# X_Axis_Stepper_Motor_Driver.net
KiCad netlist of a schematic drawn in Altium Designer
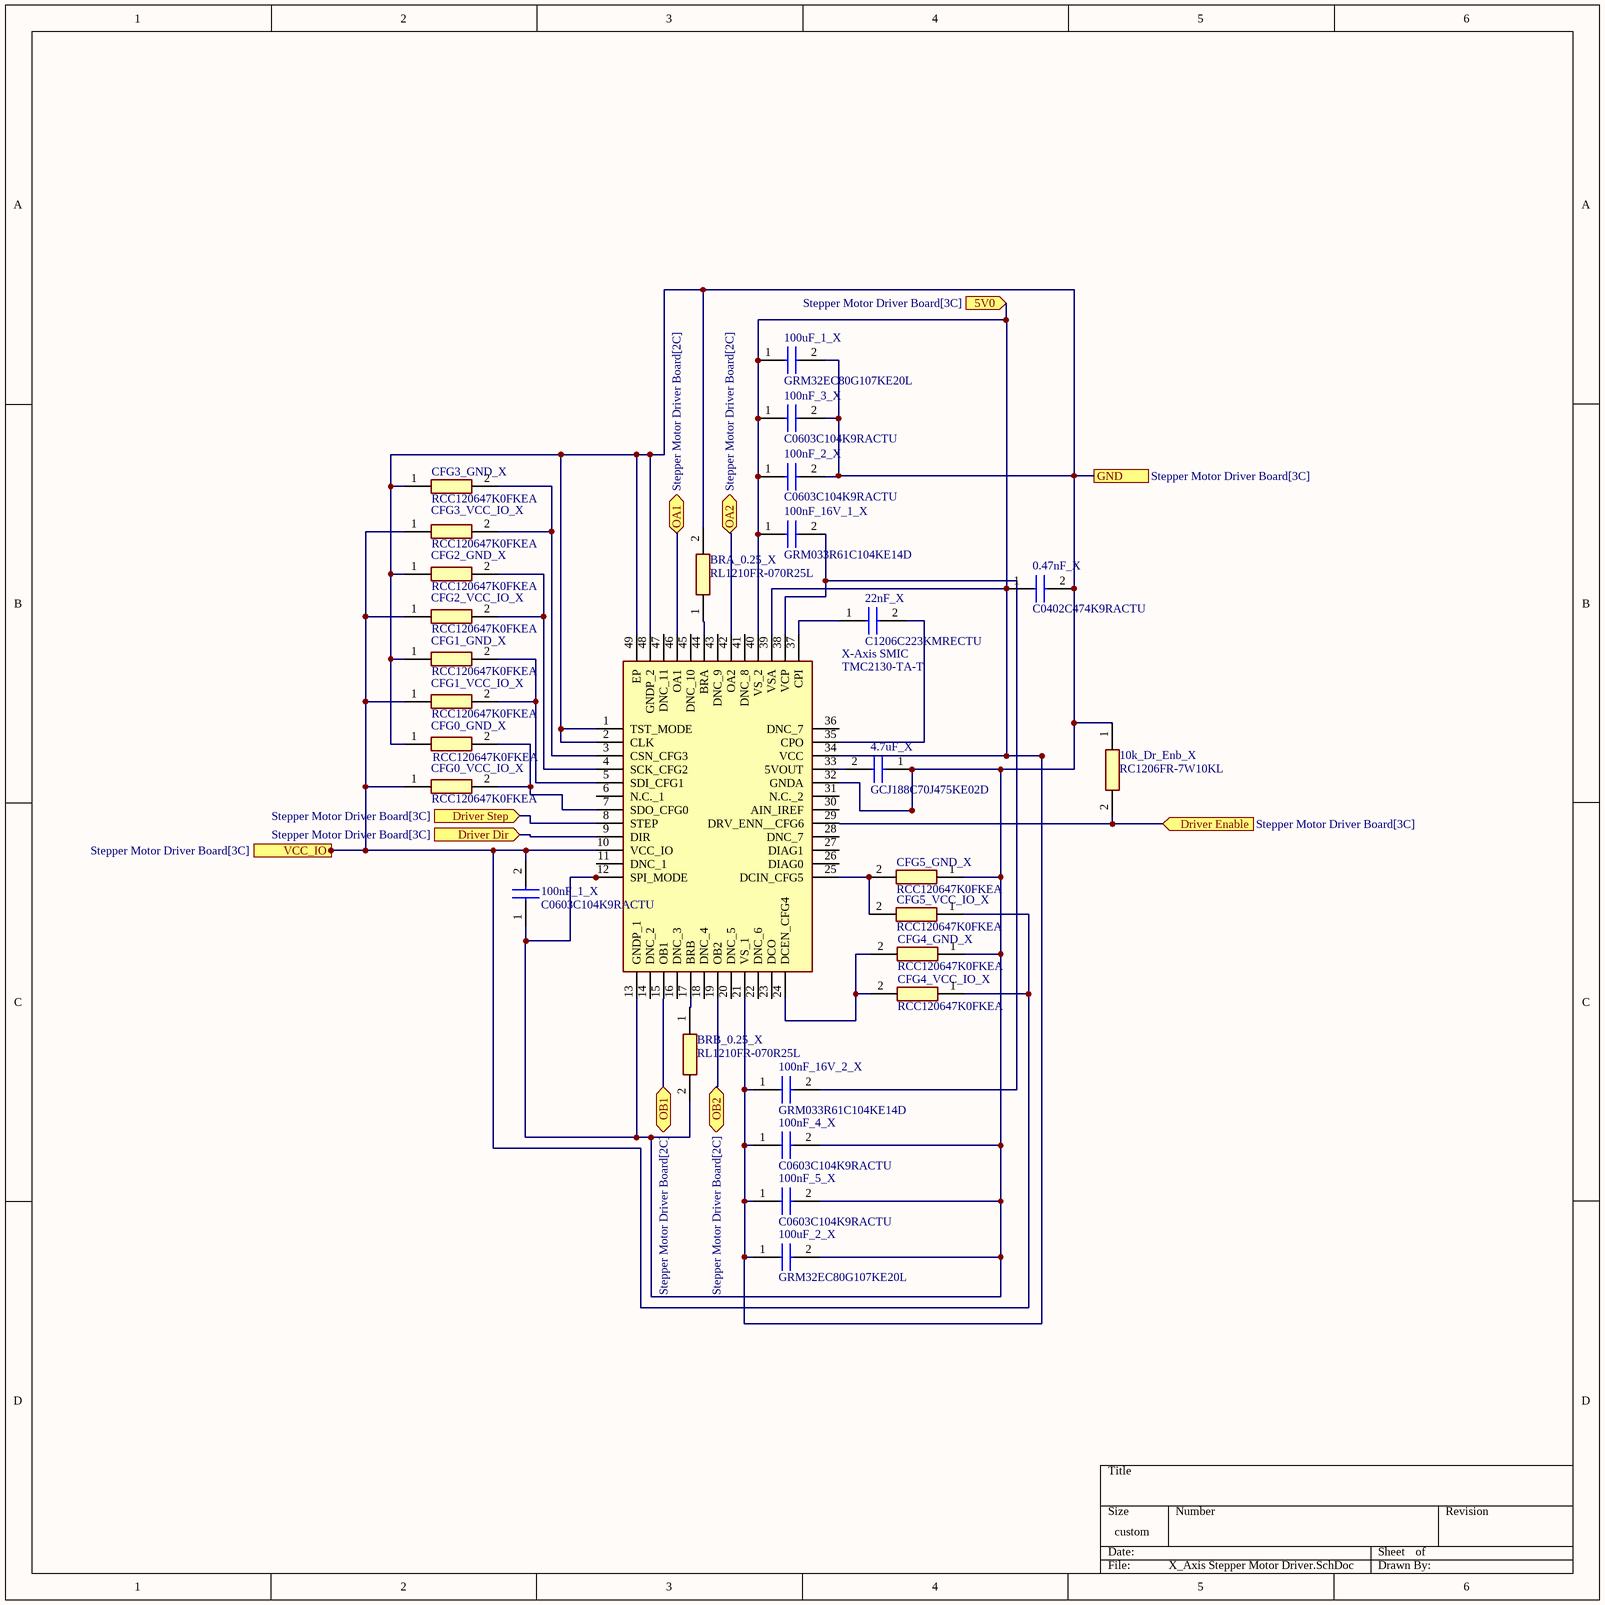
[diagram p0: X_Axis Stepper Motor Driver.SchDoc]

(export (version "E")
  (design (tool "Eeschema 10.0.6"))
  (components
    (comp (ref "0.47nF_X")
      (value "C0402C474K9RACTU")
      (footprint "SamacSys:CAPC1005X55N")
      (description "Capacitor")
      (fields (field (name "MOUSER PART NUMBER") "80-C0402C474K9RACTU"))
      (libsource (lib "*") (part "C0402C474K9RACTU"))
    )
    (comp (ref "4.7uF_X")
      (value "GCJ188C70J475KE02D")
      (footprint "SamacSys:CAPC1608X100N")
      (description "Capacitor")
      (fields (field (name "MOUSER PART NUMBER") "81-GCJ188C70J475KE2D"))
      (libsource (lib "*") (part "GCJ188C70J475KE02D"))
    )
    (comp (ref "10k_Dr_Enb_X")
      (value "RC1206FR-7W10KL")
      (footprint "SamacSys:RESC3116X65N")
      (description "Resistor")
      (libsource (lib "*") (part "RC1206FR-7W10KL"))
    )
    (comp (ref "22nF_X")
      (value "C1206C223KMRECTU")
      (footprint "SamacSys:C1206")
      (description "Capacitor")
      (fields (field (name "MOUSER PART NUMBER") "80-C1206C223KMRECTU"))
      (libsource (lib "*") (part "C1206C223KMRECTU"))
    )
    (comp (ref "100nF_1_X")
      (value "C0603C104K9RACTU")
      (footprint "SamacSys:C0603")
      (description "Capacitor")
      (fields (field (name "MOUSER PART NUMBER") "80-C0603C104K9R"))
      (libsource (lib "*") (part "C0603C104K9RACTU"))
    )
    (comp (ref "100nF_2_X")
      (value "C0603C104K9RACTU")
      (footprint "SamacSys:C0603")
      (description "Capacitor")
      (fields (field (name "MOUSER PART NUMBER") "80-C0603C104K9R"))
      (libsource (lib "*") (part "C0603C104K9RACTU"))
    )
    (comp (ref "100nF_3_X")
      (value "C0603C104K9RACTU")
      (footprint "SamacSys:C0603")
      (description "Capacitor")
      (fields (field (name "MOUSER PART NUMBER") "80-C0603C104K9R"))
      (libsource (lib "*") (part "C0603C104K9RACTU"))
    )
    (comp (ref "100nF_4_X")
      (value "C0603C104K9RACTU")
      (footprint "SamacSys:C0603")
      (description "Capacitor")
      (fields (field (name "MOUSER PART NUMBER") "80-C0603C104K9R"))
      (libsource (lib "*") (part "C0603C104K9RACTU"))
    )
    (comp (ref "100nF_5_X")
      (value "C0603C104K9RACTU")
      (footprint "SamacSys:C0603")
      (description "Capacitor")
      (fields (field (name "MOUSER PART NUMBER") "80-C0603C104K9R"))
      (libsource (lib "*") (part "C0603C104K9RACTU"))
    )
    (comp (ref "100nF_16V_1_X")
      (value "GRM033R61C104KE14D")
      (footprint "SamacSys:CAPC0603X33N")
      (description "Capacitor")
      (fields (field (name "MOUSER PART NUMBER") "81-GRM033R61C104KE4D"))
      (libsource (lib "*") (part "GRM033R61C104KE14D"))
    )
    (comp (ref "100nF_16V_2_X")
      (value "GRM033R61C104KE14D")
      (footprint "SamacSys:CAPC0603X33N")
      (description "Capacitor")
      (fields (field (name "MOUSER PART NUMBER") "81-GRM033R61C104KE4D"))
      (libsource (lib "*") (part "GRM033R61C104KE14D"))
    )
    (comp (ref "100uF_1_X")
      (value "GRM32EC80G107KE20L")
      (footprint "SamacSys:CAPC3225X270N")
      (description "Capacitor")
      (fields (field (name "MOUSER PART NUMBER") "81-GRM32EC80G107KE0L"))
      (libsource (lib "*") (part "GRM32EC80G107KE20L"))
    )
    (comp (ref "100uF_2_X")
      (value "GRM32EC80G107KE20L")
      (footprint "SamacSys:CAPC3225X270N")
      (description "Capacitor")
      (fields (field (name "MOUSER PART NUMBER") "81-GRM32EC80G107KE0L"))
      (libsource (lib "*") (part "GRM32EC80G107KE20L"))
    )
    (comp (ref "BRA_0.25_X")
      (value "RL1210FR-070R25L")
      (footprint "SamacSys:RESC3126X65N")
      (description "Resistor")
      (fields (field (name "MOUSER PART NUMBER") "603-RL1210FR-070R25L"))
      (libsource (lib "") (part "RL1210FR-070R25L_1"))
    )
    (comp (ref "BRB_0.25_X")
      (value "RL1210FR-070R25L")
      (footprint "SamacSys:RESC3126X65N")
      (description "Resistor")
      (fields (field (name "MOUSER PART NUMBER") "603-RL1210FR-070R25L"))
      (libsource (lib "*") (part "RL1210FR-070R25L"))
    )
    (comp (ref "CFG0_GND_X")
      (value "RCC120647K0FKEA")
      (footprint "SamacSys:RCC1206_e3")
      (description "Resistor")
      (fields (field (name "MOUSER PART NUMBER") "71-RCC120647K0FKEA"))
      (libsource (lib "") (part "RCC120647K0FKEA_1"))
    )
    (comp (ref "CFG0_VCC_IO_X")
      (value "RCC120647K0FKEA")
      (footprint "SamacSys:RCC1206_e3")
      (description "Resistor")
      (fields (field (name "MOUSER PART NUMBER") "71-RCC120647K0FKEA"))
      (libsource (lib "") (part "RCC120647K0FKEA_1"))
    )
    (comp (ref "CFG1_GND_X")
      (value "RCC120647K0FKEA")
      (footprint "SamacSys:RCC1206_e3")
      (description "Resistor")
      (fields (field (name "MOUSER PART NUMBER") "71-RCC120647K0FKEA"))
      (libsource (lib "") (part "RCC120647K0FKEA_1"))
    )
    (comp (ref "CFG1_VCC_IO_X")
      (value "RCC120647K0FKEA")
      (footprint "SamacSys:RCC1206_e3")
      (description "Resistor")
      (fields (field (name "MOUSER PART NUMBER") "71-RCC120647K0FKEA"))
      (libsource (lib "") (part "RCC120647K0FKEA_1"))
    )
    (comp (ref "CFG2_GND_X")
      (value "RCC120647K0FKEA")
      (footprint "SamacSys:RCC1206_e3")
      (description "Resistor")
      (fields (field (name "MOUSER PART NUMBER") "71-RCC120647K0FKEA"))
      (libsource (lib "") (part "RCC120647K0FKEA_1"))
    )
    (comp (ref "CFG2_VCC_IO_X")
      (value "RCC120647K0FKEA")
      (footprint "SamacSys:RCC1206_e3")
      (description "Resistor")
      (fields (field (name "MOUSER PART NUMBER") "71-RCC120647K0FKEA"))
      (libsource (lib "") (part "RCC120647K0FKEA_1"))
    )
    (comp (ref "CFG3_GND_X")
      (value "RCC120647K0FKEA")
      (footprint "SamacSys:RCC1206_e3")
      (description "Resistor")
      (fields (field (name "MOUSER PART NUMBER") "71-RCC120647K0FKEA"))
      (libsource (lib "") (part "RCC120647K0FKEA_1"))
    )
    (comp (ref "CFG3_VCC_IO_X")
      (value "RCC120647K0FKEA")
      (footprint "SamacSys:RCC1206_e3")
      (description "Resistor")
      (fields (field (name "MOUSER PART NUMBER") "71-RCC120647K0FKEA"))
      (libsource (lib "") (part "RCC120647K0FKEA_1"))
    )
    (comp (ref "CFG4_GND_X")
      (value "RCC120647K0FKEA")
      (footprint "SamacSys:RCC1206_e3")
      (description "Resistor")
      (fields (field (name "MOUSER PART NUMBER") "71-RCC120647K0FKEA"))
      (libsource (lib "*") (part "RCC120647K0FKEA"))
    )
    (comp (ref "CFG4_VCC_IO_X")
      (value "RCC120647K0FKEA")
      (footprint "SamacSys:RCC1206_e3")
      (description "Resistor")
      (fields (field (name "MOUSER PART NUMBER") "71-RCC120647K0FKEA"))
      (libsource (lib "*") (part "RCC120647K0FKEA"))
    )
    (comp (ref "CFG5_GND_X")
      (value "RCC120647K0FKEA")
      (footprint "SamacSys:RCC1206_e3")
      (description "Resistor")
      (fields (field (name "MOUSER PART NUMBER") "71-RCC120647K0FKEA"))
      (libsource (lib "") (part "RCC120647K0FKEA_2"))
    )
    (comp (ref "CFG5_VCC_IO_X")
      (value "RCC120647K0FKEA")
      (footprint "SamacSys:RCC1206_e3")
      (description "Resistor")
      (fields (field (name "MOUSER PART NUMBER") "71-RCC120647K0FKEA"))
      (libsource (lib "*") (part "RCC120647K0FKEA"))
    )
    (comp (ref "X-Axis SMIC")
      (value "TMC2130-TA-T")
      (footprint "SamacSys:QFP50P900X900X120-49N")
      (description "Integrated Circuit")
      (fields (field (name "MOUSER PART NUMBER") "700-TMC2130-TA-T"))
      (libsource (lib "*") (part "TMC2130-TA-T"))
    )
  )
  (nets
    (net (code "1") (name "/5V0") (class "Default")
      (node (ref "0.47nF_X") (pin "1") (pinfunction "1_1") (pintype "passive"))
      (node (ref "100nF_16V_1_X") (pin "1") (pinfunction "1_1") (pintype "passive"))
      (node (ref "100nF_16V_2_X") (pin "1") (pinfunction "1_1") (pintype "passive"))
      (node (ref "100nF_2_X") (pin "1") (pinfunction "1_1") (pintype "passive"))
      (node (ref "100nF_3_X") (pin "1") (pinfunction "1_1") (pintype "passive"))
      (node (ref "100nF_4_X") (pin "1") (pinfunction "1_1") (pintype "passive"))
      (node (ref "100nF_5_X") (pin "1") (pinfunction "1_1") (pintype "passive"))
      (node (ref "100uF_1_X") (pin "1") (pinfunction "1_1") (pintype "passive"))
      (node (ref "100uF_2_X") (pin "1") (pinfunction "1_1") (pintype "passive"))
      (node (ref "X-Axis SMIC") (pin "21") (pinfunction "VS_1_21") (pintype "passive"))
      (node (ref "X-Axis SMIC") (pin "34") (pinfunction "VCC_34") (pintype "passive"))
      (node (ref "X-Axis SMIC") (pin "39") (pinfunction "VSA_39") (pintype "passive"))
      (node (ref "X-Axis SMIC") (pin "40") (pinfunction "VS_2_40") (pintype "passive"))
    )
    (net (code "2") (name "/Driver Dir") (class "Default")
      (node (ref "X-Axis SMIC") (pin "9") (pinfunction "DIR_9") (pintype "passive"))
    )
    (net (code "3") (name "/Driver Enable") (class "Default")
      (node (ref "10k_Dr_Enb_X") (pin "2") (pinfunction "2_2") (pintype "passive"))
      (node (ref "X-Axis SMIC") (pin "29") (pinfunction "DRV_ENN__CFG6_29") (pintype "passive"))
    )
    (net (code "4") (name "/Driver Step") (class "Default")
      (node (ref "X-Axis SMIC") (pin "8") (pinfunction "STEP_8") (pintype "passive"))
    )
    (net (code "5") (name "/GND") (class "Default")
      (node (ref "0.47nF_X") (pin "2") (pinfunction "2_2") (pintype "passive"))
      (node (ref "100nF_1_X") (pin "1") (pinfunction "1_1") (pintype "passive"))
      (node (ref "100nF_2_X") (pin "2") (pinfunction "2_2") (pintype "passive"))
      (node (ref "100nF_3_X") (pin "2") (pinfunction "2_2") (pintype "passive"))
      (node (ref "100nF_4_X") (pin "2") (pinfunction "2_2") (pintype "passive"))
      (node (ref "100nF_5_X") (pin "2") (pinfunction "2_2") (pintype "passive"))
      (node (ref "100uF_1_X") (pin "2") (pinfunction "2_2") (pintype "passive"))
      (node (ref "100uF_2_X") (pin "2") (pinfunction "2_2") (pintype "passive"))
      (node (ref "10k_Dr_Enb_X") (pin "1") (pinfunction "1_1") (pintype "passive"))
      (node (ref "4.7uF_X") (pin "1") (pinfunction "1_1") (pintype "passive"))
      (node (ref "BRA_0.25_X") (pin "2") (pinfunction "2_2") (pintype "passive"))
      (node (ref "BRB_0.25_X") (pin "2") (pinfunction "2_2") (pintype "passive"))
      (node (ref "CFG0_GND_X") (pin "1") (pinfunction "1_1") (pintype "passive"))
      (node (ref "CFG1_GND_X") (pin "1") (pinfunction "1_1") (pintype "passive"))
      (node (ref "CFG2_GND_X") (pin "1") (pinfunction "1_1") (pintype "passive"))
      (node (ref "CFG3_GND_X") (pin "1") (pinfunction "1_1") (pintype "passive"))
      (node (ref "CFG4_GND_X") (pin "1") (pinfunction "1_1") (pintype "passive"))
      (node (ref "CFG5_GND_X") (pin "1") (pinfunction "1_1") (pintype "passive"))
      (node (ref "X-Axis SMIC") (pin "1") (pinfunction "TST_MODE_1") (pintype "passive"))
      (node (ref "X-Axis SMIC") (pin "12") (pinfunction "SPI_MODE_12") (pintype "passive"))
      (node (ref "X-Axis SMIC") (pin "13") (pinfunction "GNDP_1_13") (pintype "passive"))
      (node (ref "X-Axis SMIC") (pin "2") (pinfunction "CLK_2") (pintype "passive"))
      (node (ref "X-Axis SMIC") (pin "32") (pinfunction "GNDA_32") (pintype "passive"))
      (node (ref "X-Axis SMIC") (pin "48") (pinfunction "GNDP_2_48") (pintype "passive"))
      (node (ref "X-Axis SMIC") (pin "49") (pinfunction "EP_49") (pintype "passive"))
    )
    (net (code "6") (name "/OA1") (class "Default")
      (node (ref "X-Axis SMIC") (pin "46") (pinfunction "OA1_46") (pintype "passive"))
    )
    (net (code "7") (name "/OA2") (class "Default")
      (node (ref "X-Axis SMIC") (pin "42") (pinfunction "OA2_42") (pintype "passive"))
    )
    (net (code "8") (name "/OB1") (class "Default")
      (node (ref "X-Axis SMIC") (pin "15") (pinfunction "OB1_15") (pintype "passive"))
    )
    (net (code "9") (name "/OB2") (class "Default")
      (node (ref "X-Axis SMIC") (pin "19") (pinfunction "OB2_19") (pintype "passive"))
    )
    (net (code "10") (name "/VCC_IO") (class "Default")
      (node (ref "100nF_1_X") (pin "2") (pinfunction "2_2") (pintype "passive"))
      (node (ref "CFG0_VCC_IO_X") (pin "1") (pinfunction "1_1") (pintype "passive"))
      (node (ref "CFG1_VCC_IO_X") (pin "1") (pinfunction "1_1") (pintype "passive"))
      (node (ref "CFG2_VCC_IO_X") (pin "1") (pinfunction "1_1") (pintype "passive"))
      (node (ref "CFG3_VCC_IO_X") (pin "1") (pinfunction "1_1") (pintype "passive"))
      (node (ref "CFG4_VCC_IO_X") (pin "1") (pinfunction "1_1") (pintype "passive"))
      (node (ref "CFG5_VCC_IO_X") (pin "1") (pinfunction "1_1") (pintype "passive"))
      (node (ref "X-Axis SMIC") (pin "10") (pinfunction "VCC_IO_10") (pintype "passive"))
    )
    (net (code "11") (name "Net-(X-Axis SMIC-5VOUT)") (class "Default")
      (node (ref "4.7uF_X") (pin "2") (pinfunction "2_2") (pintype "passive"))
      (node (ref "X-Axis SMIC") (pin "33") (pinfunction "5VOUT_33") (pintype "passive"))
    )
    (net (code "12") (name "Net-(X-Axis SMIC-BRA)") (class "Default")
      (node (ref "BRA_0.25_X") (pin "1") (pinfunction "1_1") (pintype "passive"))
      (node (ref "X-Axis SMIC") (pin "44") (pinfunction "BRA_44") (pintype "passive"))
    )
    (net (code "13") (name "Net-(X-Axis SMIC-BRB)") (class "Default")
      (node (ref "BRB_0.25_X") (pin "1") (pinfunction "1_1") (pintype "passive"))
      (node (ref "X-Axis SMIC") (pin "17") (pinfunction "BRB_17") (pintype "passive"))
    )
    (net (code "14") (name "Net-(X-Axis SMIC-CPI)") (class "Default")
      (node (ref "22nF_X") (pin "1") (pinfunction "1_1") (pintype "passive"))
      (node (ref "X-Axis SMIC") (pin "37") (pinfunction "CPI_37") (pintype "passive"))
    )
    (net (code "15") (name "Net-(X-Axis SMIC-CPO)") (class "Default")
      (node (ref "22nF_X") (pin "2") (pinfunction "2_2") (pintype "passive"))
      (node (ref "X-Axis SMIC") (pin "35") (pinfunction "CPO_35") (pintype "passive"))
    )
    (net (code "16") (name "Net-(X-Axis SMIC-CSN_CFG3)") (class "Default")
      (node (ref "CFG3_GND_X") (pin "2") (pinfunction "2_2") (pintype "passive"))
      (node (ref "CFG3_VCC_IO_X") (pin "2") (pinfunction "2_2") (pintype "passive"))
      (node (ref "X-Axis SMIC") (pin "3") (pinfunction "CSN_CFG3_3") (pintype "passive"))
    )
    (net (code "17") (name "Net-(X-Axis SMIC-DCEN_CFG4)") (class "Default")
      (node (ref "CFG4_GND_X") (pin "2") (pinfunction "2_2") (pintype "passive"))
      (node (ref "CFG4_VCC_IO_X") (pin "2") (pinfunction "2_2") (pintype "passive"))
      (node (ref "X-Axis SMIC") (pin "24") (pinfunction "DCEN_CFG4_24") (pintype "passive"))
    )
    (net (code "18") (name "Net-(X-Axis SMIC-DCIN_CFG5)") (class "Default")
      (node (ref "CFG5_GND_X") (pin "2") (pinfunction "2_2") (pintype "passive"))
      (node (ref "CFG5_VCC_IO_X") (pin "2") (pinfunction "2_2") (pintype "passive"))
      (node (ref "X-Axis SMIC") (pin "25") (pinfunction "DCIN_CFG5_25") (pintype "passive"))
    )
    (net (code "19") (name "Net-(X-Axis SMIC-SCK_CFG2)") (class "Default")
      (node (ref "CFG2_GND_X") (pin "2") (pinfunction "2_2") (pintype "passive"))
      (node (ref "CFG2_VCC_IO_X") (pin "2") (pinfunction "2_2") (pintype "passive"))
      (node (ref "X-Axis SMIC") (pin "4") (pinfunction "SCK_CFG2_4") (pintype "passive"))
    )
    (net (code "20") (name "Net-(X-Axis SMIC-SDI_CFG1)") (class "Default")
      (node (ref "CFG1_GND_X") (pin "2") (pinfunction "2_2") (pintype "passive"))
      (node (ref "CFG1_VCC_IO_X") (pin "2") (pinfunction "2_2") (pintype "passive"))
      (node (ref "X-Axis SMIC") (pin "5") (pinfunction "SDI_CFG1_5") (pintype "passive"))
    )
    (net (code "21") (name "Net-(X-Axis SMIC-SDO_CFG0)") (class "Default")
      (node (ref "CFG0_GND_X") (pin "2") (pinfunction "2_2") (pintype "passive"))
      (node (ref "CFG0_VCC_IO_X") (pin "2") (pinfunction "2_2") (pintype "passive"))
      (node (ref "X-Axis SMIC") (pin "7") (pinfunction "SDO_CFG0_7") (pintype "passive"))
    )
    (net (code "22") (name "Net-(X-Axis SMIC-VCP)") (class "Default")
      (node (ref "100nF_16V_1_X") (pin "2") (pinfunction "2_2") (pintype "passive"))
      (node (ref "100nF_16V_2_X") (pin "2") (pinfunction "2_2") (pintype "passive"))
      (node (ref "X-Axis SMIC") (pin "38") (pinfunction "VCP_38") (pintype "passive"))
    )
    (net (code "23") (name "unconnected-(X-Axis SMIC-AIN_IREF-Pad30)") (class "Default")
      (node (ref "X-Axis SMIC") (pin "30") (pinfunction "AIN_IREF_30") (pintype "passive"))
    )
    (net (code "24") (name "unconnected-(X-Axis SMIC-DCO-Pad23)") (class "Default")
      (node (ref "X-Axis SMIC") (pin "23") (pinfunction "DCO_23") (pintype "passive"))
    )
    (net (code "25") (name "unconnected-(X-Axis SMIC-DIAG0-Pad26)") (class "Default")
      (node (ref "X-Axis SMIC") (pin "26") (pinfunction "DIAG0_26") (pintype "passive"))
    )
    (net (code "26") (name "unconnected-(X-Axis SMIC-DIAG1-Pad27)") (class "Default")
      (node (ref "X-Axis SMIC") (pin "27") (pinfunction "DIAG1_27") (pintype "passive"))
    )
    (net (code "27") (name "unconnected-(X-Axis SMIC-DNC_1-Pad11)") (class "Default")
      (node (ref "X-Axis SMIC") (pin "11") (pinfunction "DNC_1_11") (pintype "passive"))
    )
    (net (code "28") (name "unconnected-(X-Axis SMIC-DNC_2-Pad14)") (class "Default")
      (node (ref "X-Axis SMIC") (pin "14") (pinfunction "DNC_2_14") (pintype "passive"))
    )
    (net (code "29") (name "unconnected-(X-Axis SMIC-DNC_3-Pad16)") (class "Default")
      (node (ref "X-Axis SMIC") (pin "16") (pinfunction "DNC_3_16") (pintype "passive"))
    )
    (net (code "30") (name "unconnected-(X-Axis SMIC-DNC_4-Pad18)") (class "Default")
      (node (ref "X-Axis SMIC") (pin "18") (pinfunction "DNC_4_18") (pintype "passive"))
    )
    (net (code "31") (name "unconnected-(X-Axis SMIC-DNC_5-Pad20)") (class "Default")
      (node (ref "X-Axis SMIC") (pin "20") (pinfunction "DNC_5_20") (pintype "passive"))
    )
    (net (code "32") (name "unconnected-(X-Axis SMIC-DNC_6-Pad22)") (class "Default")
      (node (ref "X-Axis SMIC") (pin "22") (pinfunction "DNC_6_22") (pintype "passive"))
    )
    (net (code "33") (name "unconnected-(X-Axis SMIC-DNC_7-Pad28)") (class "Default")
      (node (ref "X-Axis SMIC") (pin "28") (pinfunction "DNC_7_28") (pintype "passive"))
    )
    (net (code "34") (name "unconnected-(X-Axis SMIC-DNC_7-Pad36)") (class "Default")
      (node (ref "X-Axis SMIC") (pin "36") (pinfunction "DNC_7_36") (pintype "passive"))
    )
    (net (code "35") (name "unconnected-(X-Axis SMIC-DNC_8-Pad41)") (class "Default")
      (node (ref "X-Axis SMIC") (pin "41") (pinfunction "DNC_8_41") (pintype "passive"))
    )
    (net (code "36") (name "unconnected-(X-Axis SMIC-DNC_9-Pad43)") (class "Default")
      (node (ref "X-Axis SMIC") (pin "43") (pinfunction "DNC_9_43") (pintype "passive"))
    )
    (net (code "37") (name "unconnected-(X-Axis SMIC-DNC_10-Pad45)") (class "Default")
      (node (ref "X-Axis SMIC") (pin "45") (pinfunction "DNC_10_45") (pintype "passive"))
    )
    (net (code "38") (name "unconnected-(X-Axis SMIC-DNC_11-Pad47)") (class "Default")
      (node (ref "X-Axis SMIC") (pin "47") (pinfunction "DNC_11_47") (pintype "passive"))
    )
    (net (code "39") (name "unconnected-(X-Axis SMIC-N.C._1-Pad6)") (class "Default")
      (node (ref "X-Axis SMIC") (pin "6") (pinfunction "N.C._1_6") (pintype "passive"))
    )
    (net (code "40") (name "unconnected-(X-Axis SMIC-N.C._2-Pad31)") (class "Default")
      (node (ref "X-Axis SMIC") (pin "31") (pinfunction "N.C._2_31") (pintype "passive"))
    )
  )
)
